# INCUBA_1_3.net
KiCad netlist of a schematic drawn in Altium Designer
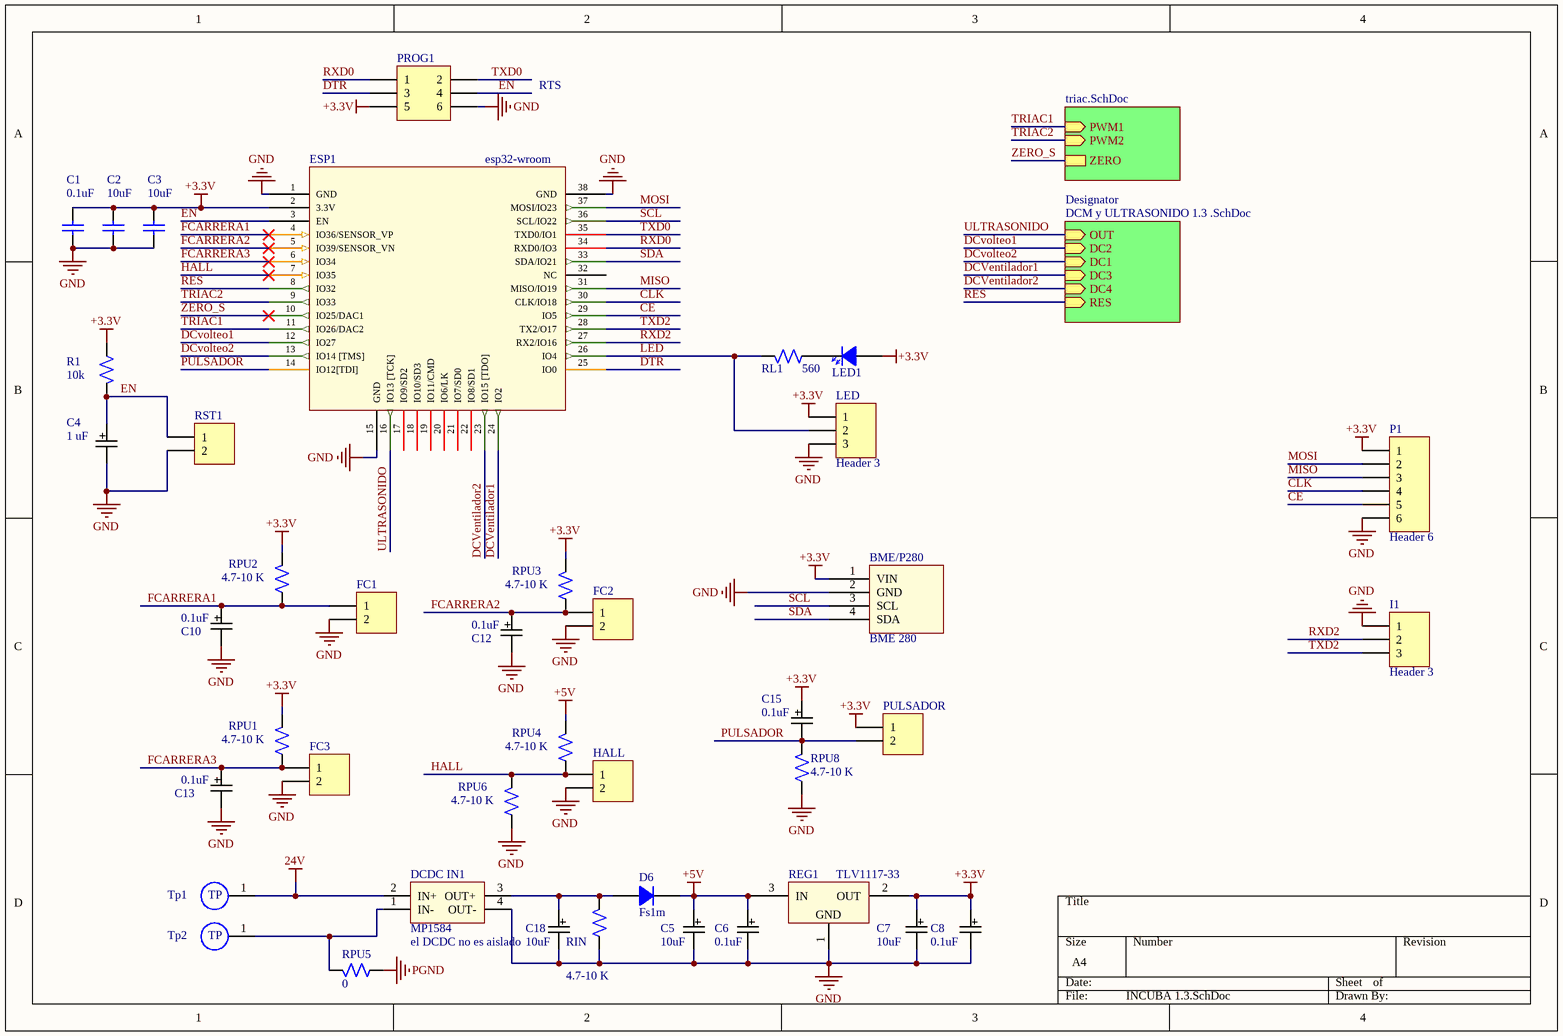
[diagram p0: INCUBA 1.3.SchDoc]

(export (version "E")
  (design (tool "Eeschema 10.0.6"))
  (components
    (comp (ref "BME/P280") (value "BME 280") (footprint "bme280") (libsource (lib "daniel") (part "BME 280")))
    (comp (ref "C1")
      (value "0.1uF")
      (footprint "0805")
      (description "Capacitor")
      (fields (field (name "PUBLISHER") "Altium Limited"))
      (libsource (lib "marcelo") (part "Cap SMD"))
    )
    (comp (ref "C2")
      (value "10uF")
      (footprint "0805")
      (description "Capacitor")
      (fields (field (name "PUBLISHER") "Altium Limited"))
      (libsource (lib "marcelo") (part "Cap SMD"))
    )
    (comp (ref "C3")
      (value "10uF")
      (footprint "0805")
      (description "Capacitor")
      (fields (field (name "PUBLISHER") "Altium Limited"))
      (libsource (lib "marcelo") (part "Cap SMD"))
    )
    (comp (ref "C4")
      (value "1 uF")
      (footprint "0805")
      (description "Capacitor")
      (libsource (lib "daniel") (part "Capacitor"))
    )
    (comp (ref "C5")
      (value "10uF")
      (footprint "0805")
      (description "Capacitor")
      (libsource (lib "daniel") (part "Capacitor"))
    )
    (comp (ref "C6")
      (value "0.1uF")
      (footprint "0805")
      (description "Capacitor")
      (libsource (lib "daniel") (part "Capacitor"))
    )
    (comp (ref "C7")
      (value "10uF")
      (footprint "0805")
      (description "100UFX6.3V 10%. B=3528 (1210) TAN.SMD AVX Codigo Elemon CA3388050")
      (fields (field (name "Comment") "Capacitor"))
      (libsource (lib "daniel") (part "Capacitor"))
    )
    (comp (ref "C8")
      (value "0.1uF")
      (footprint "0805")
      (description "Capacitor")
      (libsource (lib "daniel") (part "Capacitor"))
    )
    (comp (ref "C10")
      (value "0.1uF")
      (footprint "0805")
      (description "Capacitor")
      (libsource (lib "daniel") (part "Capacitor"))
    )
    (comp (ref "C12")
      (value "0.1uF")
      (footprint "0805")
      (description "Capacitor")
      (libsource (lib "daniel") (part "Capacitor"))
    )
    (comp (ref "C13")
      (value "0.1uF")
      (footprint "0805")
      (description "Capacitor")
      (libsource (lib "daniel") (part "Capacitor"))
    )
    (comp (ref "C15")
      (value "0.1uF")
      (footprint "0805")
      (description "Capacitor")
      (libsource (lib "daniel") (part "Capacitor"))
    )
    (comp (ref "C18")
      (value "10uF")
      (footprint "0805")
      (description "Capacitor")
      (libsource (lib "daniel") (part "Capacitor"))
    )
    (comp (ref "D6")
      (value "Fs1m")
      (footprint "DO-214AC")
      (description "DSK14 , US1M. Fs1m")
      (fields (field (name "PUBLISHER") "Altium Limited"))
      (libsource (lib "daniel") (part "Diodo"))
    )
    (comp (ref "DCDC IN1") (value "MP1584") (footprint "MP1584") (libsource (lib "daniel") (part "MP1584")))
    (comp (ref "ESP1")
      (value "esp32-wroom")
      (footprint "esp32-wroom - modificado - sinpad")
      (libsource (lib "daniel") (part "esp32-wroom"))
    )
    (comp (ref "FC1")
      (value "Header 2")
      (footprint "HDR1X2")
      (description "Header, 2-Pin")
      (fields (field (name "PUBLISHER") "Altium Limited"))
      (libsource (lib "Miscellaneous Connectors") (part "Header 2"))
    )
    (comp (ref "FC2")
      (value "Header 2")
      (footprint "HDR1X2")
      (description "Header, 2-Pin")
      (fields (field (name "PUBLISHER") "Altium Limited"))
      (libsource (lib "Miscellaneous Connectors") (part "Header 2"))
    )
    (comp (ref "FC3")
      (value "Header 2")
      (footprint "HDR1X2")
      (description "Header, 2-Pin")
      (fields (field (name "PUBLISHER") "Altium Limited"))
      (libsource (lib "Miscellaneous Connectors") (part "Header 2"))
    )
    (comp (ref "HALL")
      (value "Header 2")
      (footprint "HDR1X2")
      (description "Header, 2-Pin")
      (fields (field (name "PUBLISHER") "Altium Limited"))
      (libsource (lib "Miscellaneous Connectors") (part "Header 2"))
    )
    (comp (ref "I1")
      (value "Header 3")
      (footprint "HDR1X3")
      (description "Header, 3-Pin")
      (fields (field (name "PUBLISHER") "Altium Limited"))
      (libsource (lib "Miscellaneous Connectors") (part "Header 3"))
    )
    (comp (ref "LED")
      (value "Header 3")
      (footprint "HDR1X3")
      (description "Header, 3-Pin")
      (fields (field (name "PUBLISHER") "Altium Limited"))
      (libsource (lib "Miscellaneous Connectors") (part "Header 3"))
    )
    (comp (ref "LED1")
      (value "LED_SMD")
      (footprint "0805 - led")
      (description "Luminic signal diode")
      (fields (field (name "PUBLISHER") "Altium Limited"))
      (libsource (lib "daniel") (part "LED_SMD"))
    )
    (comp (ref "P1")
      (value "Header 6")
      (footprint "HDR1X6")
      (description "Header, 6-Pin")
      (fields (field (name "PUBLISHER") "Altium Limited"))
      (libsource (lib "Miscellaneous Connectors") (part "Header 6"))
    )
    (comp (ref "PROG1")
      (value "Header 3X2")
      (footprint "HDR2X3")
      (description "Header, 3-Pin, Dual row")
      (fields (field (name "PUBLISHER") "Altium Limited"))
      (libsource (lib "Miscellaneous Connectors") (part "Header 3X2"))
    )
    (comp (ref "PULSADOR")
      (value "Header 2")
      (footprint "HDR1X2")
      (description "Header, 2-Pin")
      (fields (field (name "PUBLISHER") "Altium Limited"))
      (libsource (lib "Miscellaneous Connectors") (part "Header 2"))
    )
    (comp (ref "R1")
      (value "10k")
      (footprint "0805")
      (description "Resistencia  de con varios Footprint")
      (fields (field (name "Comment") "Resistencia"))
      (libsource (lib "daniel") (part "Resistencia"))
    )
    (comp (ref "REG1")
      (value "TLV1117-33")
      (footprint "SOT-223-4")
      (libsource (lib "daniel") (part "TLV1117-33"))
    )
    (comp (ref "RIN")
      (value "4.7-10 K")
      (footprint "0805")
      (description "Resistencia  de con varios Footprint")
      (fields (field (name "Comment") "Resistencia"))
      (libsource (lib "daniel") (part "Resistencia"))
    )
    (comp (ref "RL1")
      (value "560")
      (footprint "0805")
      (description "Resistencia  de con varios Footprint")
      (fields (field (name "Comment") "Resistencia"))
      (libsource (lib "daniel") (part "Resistencia"))
    )
    (comp (ref "RPU1")
      (value "4.7-10 K")
      (footprint "0805")
      (description "Resistencia  de con varios Footprint")
      (fields (field (name "Comment") "Resistencia"))
      (libsource (lib "daniel") (part "Resistencia"))
    )
    (comp (ref "RPU2")
      (value "4.7-10 K")
      (footprint "0805")
      (description "Resistencia  de con varios Footprint")
      (fields (field (name "Comment") "Resistencia"))
      (libsource (lib "daniel") (part "Resistencia"))
    )
    (comp (ref "RPU3")
      (value "4.7-10 K")
      (footprint "0805")
      (description "Resistencia  de con varios Footprint")
      (fields (field (name "Comment") "Resistencia"))
      (libsource (lib "daniel") (part "Resistencia"))
    )
    (comp (ref "RPU4")
      (value "4.7-10 K")
      (footprint "0805")
      (description "Resistencia  de con varios Footprint")
      (fields (field (name "Comment") "Resistencia"))
      (libsource (lib "daniel") (part "Resistencia"))
    )
    (comp (ref "RPU5")
      (value "0")
      (footprint "0805")
      (description "Resistencia  de con varios Footprint")
      (fields (field (name "Comment") "Resistencia"))
      (libsource (lib "daniel") (part "Resistencia"))
    )
    (comp (ref "RPU6")
      (value "4.7-10 K")
      (footprint "0805")
      (description "Resistencia  de con varios Footprint")
      (fields (field (name "Comment") "Resistencia"))
      (libsource (lib "daniel") (part "Resistencia"))
    )
    (comp (ref "RPU8")
      (value "4.7-10 K")
      (footprint "0805")
      (description "Resistencia  de con varios Footprint")
      (fields (field (name "Comment") "Resistencia"))
      (libsource (lib "daniel") (part "Resistencia"))
    )
    (comp (ref "RST1")
      (value "Header 2")
      (footprint "HDR1X2")
      (description "Header, 2-Pin")
      (fields (field (name "PUBLISHER") "Altium Limited"))
      (libsource (lib "Miscellaneous Connectors") (part "Header 2"))
    )
    (comp (ref "Tp1")
      (value "Testpoint")
      (footprint "Testpoint")
      (description "Tespoint")
      (libsource (lib "daniel") (part "Testpoint"))
    )
    (comp (ref "Tp2")
      (value "Testpoint")
      (footprint "Testpoint")
      (description "Tespoint")
      (libsource (lib "daniel") (part "Testpoint"))
    )
  )
  (nets
    (net (code "1") (name "+3.3V") (class "Default")
      (node (ref "BME/P280") (pin "1") (pinfunction "VIN_1") (pintype "passive"))
      (node (ref "C1") (pin "2") (pinfunction "2_2") (pintype "passive"))
      (node (ref "C15") (pin "2") (pinfunction "2_2") (pintype "passive"))
      (node (ref "C2") (pin "2") (pinfunction "2_2") (pintype "passive"))
      (node (ref "C3") (pin "2") (pinfunction "2_2") (pintype "passive"))
      (node (ref "C7") (pin "2") (pinfunction "2_2") (pintype "passive"))
      (node (ref "C8") (pin "2") (pinfunction "2_2") (pintype "passive"))
      (node (ref "ESP1") (pin "2") (pinfunction "3.3V_2") (pintype "passive"))
      (node (ref "LED") (pin "1") (pinfunction "1_1") (pintype "passive"))
      (node (ref "LED1") (pin "2") (pinfunction "A_2") (pintype "passive"))
      (node (ref "P1") (pin "1") (pinfunction "1_1") (pintype "passive"))
      (node (ref "PROG1") (pin "5") (pinfunction "5_5") (pintype "passive"))
      (node (ref "PULSADOR") (pin "1") (pinfunction "1_1") (pintype "passive"))
      (node (ref "R1") (pin "2") (pinfunction "2_2") (pintype "passive"))
      (node (ref "REG1") (pin "2") (pinfunction "OUT_2") (pintype "passive"))
      (node (ref "RPU1") (pin "2") (pinfunction "2_2") (pintype "passive"))
      (node (ref "RPU2") (pin "2") (pinfunction "2_2") (pintype "passive"))
      (node (ref "RPU3") (pin "2") (pinfunction "2_2") (pintype "passive"))
    )
    (net (code "2") (name "+5V") (class "Default")
      (node (ref "C5") (pin "2") (pinfunction "2_2") (pintype "passive"))
      (node (ref "C6") (pin "2") (pinfunction "2_2") (pintype "passive"))
      (node (ref "D6") (pin "1") (pinfunction "K_1") (pintype "passive"))
      (node (ref "REG1") (pin "3") (pinfunction "IN_3") (pintype "passive"))
      (node (ref "RPU4") (pin "2") (pinfunction "2_2") (pintype "passive"))
    )
    (net (code "3") (name "/CE") (class "Default")
      (node (ref "ESP1") (pin "29") (pinfunction "IO5_29") (pintype "output"))
      (node (ref "P1") (pin "5") (pinfunction "5_5") (pintype "passive"))
    )
    (net (code "4") (name "/CLK") (class "Default")
      (node (ref "ESP1") (pin "30") (pinfunction "CLK/IO18_30") (pintype "output"))
      (node (ref "P1") (pin "4") (pinfunction "4_4") (pintype "passive"))
    )
    (net (code "5") (name "/DCVentilador1") (class "Default")
      (node (ref "ESP1") (pin "24") (pinfunction "IO2_24") (pintype "output"))
    )
    (net (code "6") (name "/DCVentilador2") (class "Default")
      (node (ref "ESP1") (pin "23") (pinfunction "IO15_[TDO]_23") (pintype "output"))
    )
    (net (code "7") (name "/DCvolteo1") (class "Default")
      (node (ref "ESP1") (pin "12") (pinfunction "IO27_12") (pintype "output"))
    )
    (net (code "8") (name "/DCvolteo2") (class "Default")
      (node (ref "ESP1") (pin "13") (pinfunction "IO14_[TMS]_13") (pintype "output"))
    )
    (net (code "9") (name "/DTR") (class "Default")
      (node (ref "ESP1") (pin "25") (pinfunction "IO0_25") (pintype "passive"))
      (node (ref "PROG1") (pin "3") (pinfunction "3_3") (pintype "passive"))
    )
    (net (code "10") (name "/EN") (class "Default")
      (node (ref "C4") (pin "2") (pinfunction "2_2") (pintype "passive"))
      (node (ref "ESP1") (pin "3") (pinfunction "EN_3") (pintype "passive"))
      (node (ref "PROG1") (pin "4") (pinfunction "4_4") (pintype "passive"))
      (node (ref "R1") (pin "1") (pinfunction "1_1") (pintype "passive"))
      (node (ref "RST1") (pin "1") (pinfunction "1_1") (pintype "passive"))
    )
    (net (code "11") (name "/FCARRERA1") (class "Default")
      (node (ref "C10") (pin "2") (pinfunction "2_2") (pintype "passive"))
      (node (ref "ESP1") (pin "4") (pinfunction "IO36/SENSOR_VP_4") (pintype "input"))
      (node (ref "FC1") (pin "1") (pinfunction "1_1") (pintype "passive"))
      (node (ref "RPU2") (pin "1") (pinfunction "1_1") (pintype "passive"))
    )
    (net (code "12") (name "/FCARRERA2") (class "Default")
      (node (ref "C12") (pin "2") (pinfunction "2_2") (pintype "passive"))
      (node (ref "ESP1") (pin "5") (pinfunction "IO39/SENSOR_VN_5") (pintype "input"))
      (node (ref "FC2") (pin "1") (pinfunction "1_1") (pintype "passive"))
      (node (ref "RPU3") (pin "1") (pinfunction "1_1") (pintype "passive"))
    )
    (net (code "13") (name "/FCARRERA3") (class "Default")
      (node (ref "C13") (pin "2") (pinfunction "2_2") (pintype "passive"))
      (node (ref "ESP1") (pin "6") (pinfunction "IO34_6") (pintype "input"))
      (node (ref "FC3") (pin "1") (pinfunction "1_1") (pintype "passive"))
      (node (ref "RPU1") (pin "1") (pinfunction "1_1") (pintype "passive"))
    )
    (net (code "14") (name "/HALL") (class "Default")
      (node (ref "ESP1") (pin "7") (pinfunction "IO35_7") (pintype "input"))
      (node (ref "HALL") (pin "1") (pinfunction "1_1") (pintype "passive"))
      (node (ref "RPU4") (pin "1") (pinfunction "1_1") (pintype "passive"))
      (node (ref "RPU6") (pin "2") (pinfunction "2_2") (pintype "passive"))
    )
    (net (code "15") (name "/LED") (class "Default")
      (node (ref "ESP1") (pin "26") (pinfunction "IO4_26") (pintype "output"))
      (node (ref "LED") (pin "2") (pinfunction "2_2") (pintype "passive"))
      (node (ref "RL1") (pin "2") (pinfunction "2_2") (pintype "passive"))
    )
    (net (code "16") (name "/MISO") (class "Default")
      (node (ref "ESP1") (pin "31") (pinfunction "MISO/IO19_31") (pintype "output"))
      (node (ref "P1") (pin "3") (pinfunction "3_3") (pintype "passive"))
    )
    (net (code "17") (name "/MOSI") (class "Default")
      (node (ref "ESP1") (pin "37") (pinfunction "MOSI/IO23_37") (pintype "output"))
      (node (ref "P1") (pin "2") (pinfunction "2_2") (pintype "passive"))
    )
    (net (code "18") (name "/PULSADOR") (class "Default")
      (node (ref "C15") (pin "1") (pinfunction "1_1") (pintype "power_in"))
      (node (ref "ESP1") (pin "14") (pinfunction "IO12[TDI]_14") (pintype "passive"))
      (node (ref "PULSADOR") (pin "2") (pinfunction "2_2") (pintype "passive"))
      (node (ref "RPU8") (pin "2") (pinfunction "2_2") (pintype "passive"))
    )
    (net (code "19") (name "/RES") (class "Default")
      (node (ref "ESP1") (pin "8") (pinfunction "IO32_8") (pintype "output"))
    )
    (net (code "20") (name "/RXD0") (class "Default")
      (node (ref "ESP1") (pin "34") (pinfunction "RXD0/IO3_34") (pintype "passive"))
      (node (ref "PROG1") (pin "1") (pinfunction "1_1") (pintype "passive"))
    )
    (net (code "21") (name "/RXD2") (class "Default")
      (node (ref "ESP1") (pin "27") (pinfunction "RX2/IO16_27") (pintype "output"))
      (node (ref "I1") (pin "2") (pinfunction "2_2") (pintype "passive"))
    )
    (net (code "22") (name "/SCL") (class "Default")
      (node (ref "BME/P280") (pin "3") (pinfunction "SCL_3") (pintype "passive"))
      (node (ref "ESP1") (pin "36") (pinfunction "SCL/IO22_36") (pintype "output"))
    )
    (net (code "23") (name "/SDA") (class "Default")
      (node (ref "BME/P280") (pin "4") (pinfunction "SDA_4") (pintype "passive"))
      (node (ref "ESP1") (pin "33") (pinfunction "SDA/IO21_33") (pintype "output"))
    )
    (net (code "24") (name "/TRIAC1") (class "Default")
      (node (ref "ESP1") (pin "11") (pinfunction "IO26/DAC2_11") (pintype "output"))
    )
    (net (code "25") (name "/TRIAC2") (class "Default")
      (node (ref "ESP1") (pin "9") (pinfunction "IO33_9") (pintype "output"))
    )
    (net (code "26") (name "/TXD0") (class "Default")
      (node (ref "ESP1") (pin "35") (pinfunction "TXD0/IO1_35") (pintype "passive"))
      (node (ref "PROG1") (pin "2") (pinfunction "2_2") (pintype "passive"))
    )
    (net (code "27") (name "/TXD2") (class "Default")
      (node (ref "ESP1") (pin "28") (pinfunction "TX2/O17_28") (pintype "output"))
      (node (ref "I1") (pin "3") (pinfunction "3_3") (pintype "passive"))
    )
    (net (code "28") (name "/ULTRASONIDO") (class "Default")
      (node (ref "ESP1") (pin "16") (pinfunction "IO13_[TCK]_16") (pintype "output"))
    )
    (net (code "29") (name "/ZERO_S") (class "Default")
      (node (ref "ESP1") (pin "10") (pinfunction "IO25/DAC1_10") (pintype "output+no_connect"))
    )
    (net (code "30") (name "24V") (class "Default")
      (node (ref "DCDC IN1") (pin "2") (pinfunction "IN+_2") (pintype "passive"))
      (node (ref "Tp1") (pin "1") (pinfunction "TP_1") (pintype "passive"))
    )
    (net (code "31") (name "GND") (class "Default")
      (node (ref "BME/P280") (pin "2") (pinfunction "GND_2") (pintype "passive"))
      (node (ref "C1") (pin "1") (pinfunction "1_1") (pintype "passive"))
      (node (ref "C10") (pin "1") (pinfunction "1_1") (pintype "power_in"))
      (node (ref "C12") (pin "1") (pinfunction "1_1") (pintype "power_in"))
      (node (ref "C13") (pin "1") (pinfunction "1_1") (pintype "power_in"))
      (node (ref "C18") (pin "1") (pinfunction "1_1") (pintype "power_in"))
      (node (ref "C2") (pin "1") (pinfunction "1_1") (pintype "passive"))
      (node (ref "C3") (pin "1") (pinfunction "1_1") (pintype "passive"))
      (node (ref "C4") (pin "1") (pinfunction "1_1") (pintype "power_in"))
      (node (ref "C5") (pin "1") (pinfunction "1_1") (pintype "power_in"))
      (node (ref "C6") (pin "1") (pinfunction "1_1") (pintype "power_in"))
      (node (ref "C7") (pin "1") (pinfunction "1_1") (pintype "power_in"))
      (node (ref "C8") (pin "1") (pinfunction "1_1") (pintype "power_in"))
      (node (ref "DCDC IN1") (pin "4") (pinfunction "OUT-_4") (pintype "passive"))
      (node (ref "ESP1") (pin "1") (pinfunction "GND_1") (pintype "passive"))
      (node (ref "ESP1") (pin "15") (pinfunction "GND_15") (pintype "passive"))
      (node (ref "ESP1") (pin "38") (pinfunction "GND_38") (pintype "passive"))
      (node (ref "FC1") (pin "2") (pinfunction "2_2") (pintype "passive"))
      (node (ref "FC2") (pin "2") (pinfunction "2_2") (pintype "passive"))
      (node (ref "FC3") (pin "2") (pinfunction "2_2") (pintype "passive"))
      (node (ref "HALL") (pin "2") (pinfunction "2_2") (pintype "passive"))
      (node (ref "I1") (pin "1") (pinfunction "1_1") (pintype "passive"))
      (node (ref "LED") (pin "3") (pinfunction "3_3") (pintype "passive"))
      (node (ref "P1") (pin "6") (pinfunction "6_6") (pintype "passive"))
      (node (ref "PROG1") (pin "6") (pinfunction "6_6") (pintype "passive"))
      (node (ref "REG1") (pin "1") (pinfunction "GND_1") (pintype "passive"))
      (node (ref "RIN") (pin "1") (pinfunction "1_1") (pintype "passive"))
      (node (ref "RPU6") (pin "1") (pinfunction "1_1") (pintype "passive"))
      (node (ref "RPU8") (pin "1") (pinfunction "1_1") (pintype "passive"))
      (node (ref "RST1") (pin "2") (pinfunction "2_2") (pintype "passive"))
    )
    (net (code "32") (name "Net-(D6-A)") (class "Default")
      (node (ref "C18") (pin "2") (pinfunction "2_2") (pintype "passive"))
      (node (ref "D6") (pin "2") (pinfunction "A_2") (pintype "passive"))
      (node (ref "DCDC IN1") (pin "3") (pinfunction "OUT+_3") (pintype "passive"))
      (node (ref "RIN") (pin "2") (pinfunction "2_2") (pintype "passive"))
    )
    (net (code "33") (name "Net-(DCDC IN1-IN-)") (class "Default")
      (node (ref "DCDC IN1") (pin "1") (pinfunction "IN-_1") (pintype "passive"))
      (node (ref "RPU5") (pin "2") (pinfunction "2_2") (pintype "passive"))
      (node (ref "Tp2") (pin "1") (pinfunction "TP_1") (pintype "passive"))
    )
    (net (code "34") (name "Net-(LED1-K)") (class "Default")
      (node (ref "LED1") (pin "1") (pinfunction "K_1") (pintype "passive"))
      (node (ref "RL1") (pin "1") (pinfunction "1_1") (pintype "passive"))
    )
    (net (code "35") (name "PGND") (class "Default")
      (node (ref "RPU5") (pin "1") (pinfunction "1_1") (pintype "passive"))
    )
    (net (code "36") (name "unconnected-(ESP1-IO6{slash}LK-Pad20)") (class "Default")
      (node (ref "ESP1") (pin "20") (pinfunction "IO6/LK_20") (pintype "passive"))
    )
    (net (code "37") (name "unconnected-(ESP1-IO7{slash}SD0-Pad21)") (class "Default")
      (node (ref "ESP1") (pin "21") (pinfunction "IO7/SD0_21") (pintype "passive"))
    )
    (net (code "38") (name "unconnected-(ESP1-IO8{slash}SD1-Pad22)") (class "Default")
      (node (ref "ESP1") (pin "22") (pinfunction "IO8/SD1_22") (pintype "passive"))
    )
    (net (code "39") (name "unconnected-(ESP1-IO9{slash}SD2-Pad17)") (class "Default")
      (node (ref "ESP1") (pin "17") (pinfunction "IO9/SD2_17") (pintype "passive"))
    )
    (net (code "40") (name "unconnected-(ESP1-IO10{slash}SD3-Pad18)") (class "Default")
      (node (ref "ESP1") (pin "18") (pinfunction "IO10/SD3_18") (pintype "passive"))
    )
    (net (code "41") (name "unconnected-(ESP1-IO11{slash}CMD-Pad19)") (class "Default")
      (node (ref "ESP1") (pin "19") (pinfunction "IO11/CMD_19") (pintype "passive"))
    )
    (net (code "42") (name "unconnected-(ESP1-NC-Pad32)") (class "Default")
      (node (ref "ESP1") (pin "32") (pinfunction "NC_32") (pintype "passive"))
    )
  )
)
